# Accelerometer_3Axis-bak.net
KiCad netlist of a schematic drawn in Altium Designer
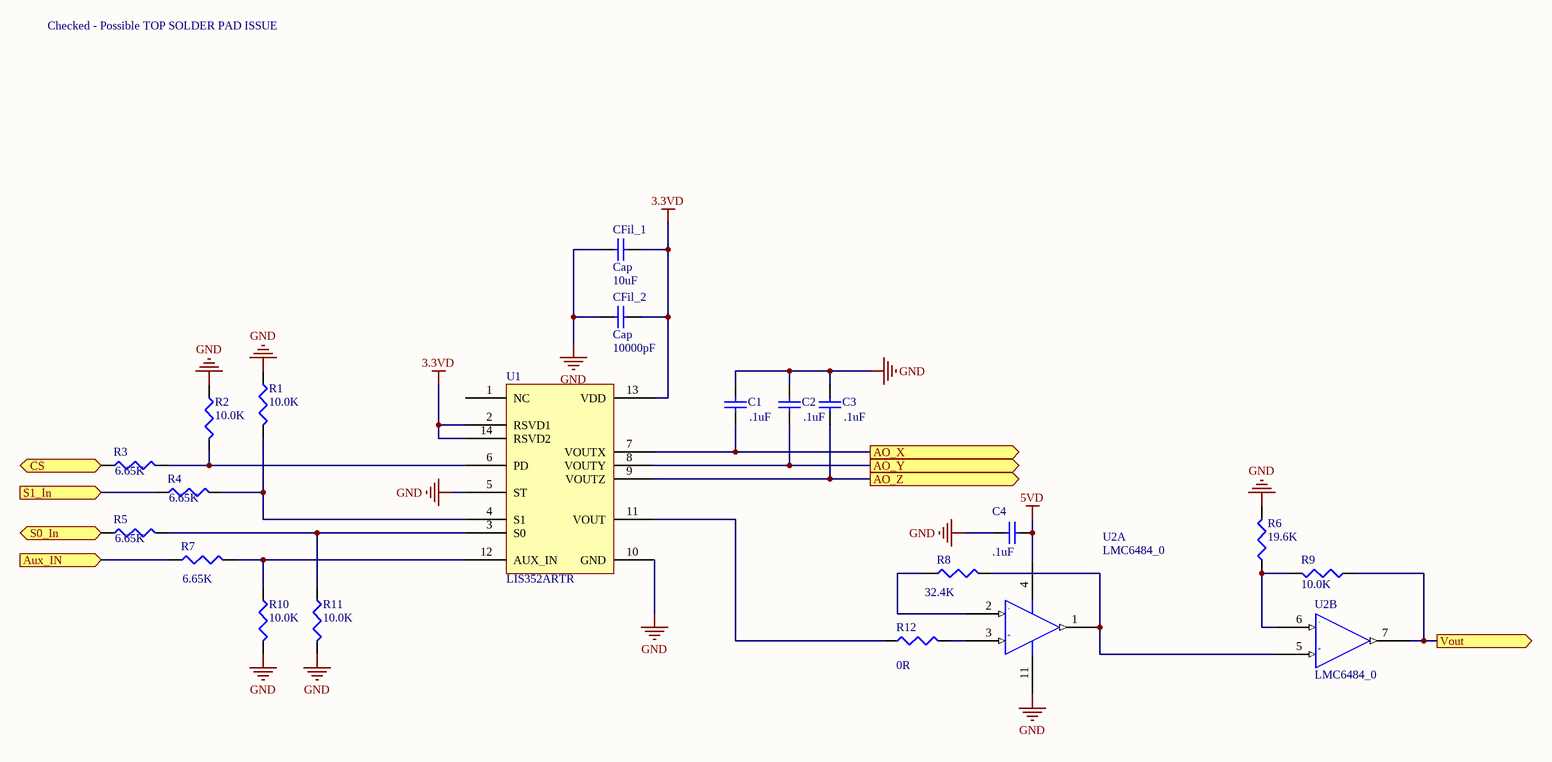
[diagram p0: Accelerometer_3Axis-bak.SchDoc]

(export (version "E")
  (design (tool "Eeschema 10.0.6"))
  (components
    (comp (ref "C1")
      (value ".1uF")
      (footprint "CAPC2012X09M")
      (description "CAP CER .1uF 50v Y5V 0805")
      (fields (field (name "TOLERANCE") "+80%/-20%") (field (name "MPN") "C0805C104Z5VACTU"))
      (libsource (lib "esd_library") (part "CAP-Y5V-.1uF-50V-+80%/-20%"))
    )
    (comp (ref "C2")
      (value ".1uF")
      (footprint "CAPC2012X09M")
      (description "CAP CER .1uF 50v Y5V 0805")
      (fields (field (name "TOLERANCE") "+80%/-20%") (field (name "MPN") "C0805C104Z5VACTU"))
      (libsource (lib "esd_library") (part "CAP-Y5V-.1uF-50V-+80%/-20%"))
    )
    (comp (ref "C3")
      (value ".1uF")
      (footprint "CAPC2012X09M")
      (description "CAP CER .1uF 50v Y5V 0805")
      (fields (field (name "TOLERANCE") "+80%/-20%") (field (name "MPN") "C0805C104Z5VACTU"))
      (libsource (lib "esd_library") (part "CAP-Y5V-.1uF-50V-+80%/-20%"))
    )
    (comp (ref "C4")
      (value ".1uF")
      (footprint "CAPC2012X09M")
      (description "CAP CER .1uF 50v X7R 0805")
      (fields (field (name "MPN") "C0805C104M5RACTU") (field (name "Comment") "Cap"))
      (libsource (lib "esd_library") (part "CAP-X7R-.1uF-50V-±20%"))
    )
    (comp (ref "CFil_1")
      (value "Cap")
      (footprint "CAPC2012X09M")
      (description "CAP CER 10uF 6.3v X5R 0805")
      (fields (field (name "ALTIUM_VALUE") "10uF") (field (name "MPN") "C0805C106K9PACTU"))
      (libsource (lib "esd_library") (part "CAP-X5R-10uF-6.3V-±10%"))
    )
    (comp (ref "CFil_2")
      (value "Cap")
      (footprint "CAPC2012X09M")
      (description "CAP CER 10000pF 50v Z5U 0805")
      (fields (field (name "ALTIUM_VALUE") "10000pF") (field (name "MPN") "C0805C103M5UACTU"))
      (libsource (lib "esd_library") (part "CAP-Z5U-10000pF-50V-±20%"))
    )
    (comp (ref "R1")
      (value "10.0K")
      (footprint "RESC2112X05M")
      (description "RES SMD 10.0K OHM 1% 1/8W 0805")
      (fields (field (name "MPN") "CRCW080510K0FKEA") (field (name "Comment") "Res3"))
      (libsource (lib "esd_library") (part "Resistor_10.0K"))
    )
    (comp (ref "R2")
      (value "10.0K")
      (footprint "RESC2112X05M")
      (description "RES SMD 10.0K OHM 1% 1/8W 0805")
      (fields (field (name "MPN") "CRCW080510K0FKEA") (field (name "Comment") "Res3"))
      (libsource (lib "esd_library") (part "Resistor_10.0K"))
    )
    (comp (ref "R3")
      (value "6.65K")
      (footprint "RESC2112X05M")
      (description "RES SMD 6.65K OHM 1% 1/8W 0805")
      (fields (field (name "MPN") "CRCW08056K65FKEA") (field (name "Comment") "Res3"))
      (libsource (lib "esd_library") (part "Resistor_6.65K"))
    )
    (comp (ref "R4")
      (value "6.65K")
      (footprint "RESC2112X05M")
      (description "RES SMD 6.65K OHM 1% 1/8W 0805")
      (fields (field (name "MPN") "CRCW08056K65FKEA") (field (name "Comment") "Res3"))
      (libsource (lib "esd_library") (part "Resistor_6.65K"))
    )
    (comp (ref "R5")
      (value "6.65K")
      (footprint "RESC2112X05M")
      (description "RES SMD 6.65K OHM 1% 1/8W 0805")
      (fields (field (name "MPN") "CRCW08056K65FKEA") (field (name "Comment") "Res3"))
      (libsource (lib "esd_library") (part "Resistor_6.65K"))
    )
    (comp (ref "R6")
      (value "19.6K")
      (footprint "RESC2112X05M")
      (description "RES SMD 19.6K OHM 1% 1/8W 0805")
      (fields (field (name "MPN") "CRCW080519K6FKEA") (field (name "Comment") "Res3"))
      (libsource (lib "esd_library (1)") (part "Resistor_19.6K"))
    )
    (comp (ref "R7")
      (value "6.65K")
      (footprint "RESC2112X05M")
      (description "RES SMD 6.65K OHM 1% 1/8W 0805")
      (fields (field (name "MPN") "CRCW08056K65FKEA") (field (name "Comment") "Res3"))
      (libsource (lib "esd_library") (part "Resistor_6.65K"))
    )
    (comp (ref "R8")
      (value "32.4K")
      (footprint "RESC2112X05M")
      (description "RES SMD 32.4K OHM 1% 1/8W 0805")
      (fields (field (name "MPN") "CRCW080532K4FKEA") (field (name "Comment") "Res3"))
      (libsource (lib "esd_library") (part "Resistor_32.4K"))
    )
    (comp (ref "R9")
      (value "10.0K")
      (footprint "RESC2112X05M")
      (description "RES SMD 10.0K OHM 1% 1/8W 0805")
      (fields (field (name "MPN") "CRCW080510K0FKEA") (field (name "Comment") "Res3"))
      (libsource (lib "esd_library") (part "Resistor_10.0K"))
    )
    (comp (ref "R10")
      (value "10.0K")
      (footprint "RESC2112X05M")
      (description "RES SMD 10.0K OHM 1% 1/8W 0805")
      (fields (field (name "MPN") "CRCW080510K0FKEA") (field (name "Comment") "Res3"))
      (libsource (lib "esd_library") (part "Resistor_10.0K"))
    )
    (comp (ref "R11")
      (value "10.0K")
      (footprint "RESC2112X05M")
      (description "RES SMD 10.0K OHM 1% 1/8W 0805")
      (fields (field (name "MPN") "CRCW080510K0FKEA") (field (name "Comment") "Res3"))
      (libsource (lib "esd_library") (part "Resistor_10.0K"))
    )
    (comp (ref "R12")
      (value "0R")
      (footprint "RESC2112X05M")
      (description "RES SMD 0 OHM 5% 1/8W 0805")
      (fields (field (name "MPN") "CRCW08050000Z0EA") (field (name "Comment") "Res3"))
      (libsource (lib "esd_library") (part "Resistor_0R_Jumper"))
    )
    (comp (ref "U1")
      (value "LIS352ARTR")
      (footprint "LGA-14-3X5MM")
      (description "IC ACCELEROMETER 3AXIS LP 14LGA")
      (libsource (lib "esd_library") (part "LIS352AR"))
    )
    (comp (ref "U2")
      (value "LMC6484_0")
      (footprint "SOIC127P600X175-14M-NS")
      (description "IC OPAMP GP 1.5MHZ RRO 14SOIC")
      (fields (field (name "MPN") "LMC6484IMX/NOPB"))
      (libsource (lib "esd_library") (part "LMC6484_0"))
    )
  )
  (nets
    (net (code "1") (name "/AO_X") (class "Default")
      (node (ref "C1") (pin "1") (pinfunction "1_1") (pintype "passive"))
      (node (ref "U1") (pin "7") (pinfunction "VOUTX_7") (pintype "passive"))
    )
    (net (code "2") (name "/AO_Y") (class "Default")
      (node (ref "C2") (pin "1") (pinfunction "1_1") (pintype "passive"))
      (node (ref "U1") (pin "8") (pinfunction "VOUTY_8") (pintype "passive"))
    )
    (net (code "3") (name "/AO_Z") (class "Default")
      (node (ref "C3") (pin "1") (pinfunction "1_1") (pintype "passive"))
      (node (ref "U1") (pin "9") (pinfunction "VOUTZ_9") (pintype "passive"))
    )
    (net (code "4") (name "/Aux_IN") (class "Default")
      (node (ref "R7") (pin "1") (pinfunction "1_1") (pintype "passive"))
    )
    (net (code "5") (name "/CS") (class "Default")
      (node (ref "R3") (pin "1") (pinfunction "1_1") (pintype "passive"))
    )
    (net (code "6") (name "/S0_In") (class "Default")
      (node (ref "R5") (pin "1") (pinfunction "1_1") (pintype "passive"))
    )
    (net (code "7") (name "/S1_In") (class "Default")
      (node (ref "R4") (pin "1") (pinfunction "1_1") (pintype "passive"))
    )
    (net (code "8") (name "/Vout") (class "Default")
      (node (ref "R9") (pin "1") (pinfunction "1_1") (pintype "passive"))
      (node (ref "U2") (pin "7") (pinfunction "OUT2_7") (pintype "output"))
    )
    (net (code "9") (name "3.3VD") (class "Default")
      (node (ref "CFil_1") (pin "1") (pinfunction "1_1") (pintype "passive"))
      (node (ref "CFil_2") (pin "1") (pinfunction "1_1") (pintype "passive"))
      (node (ref "U1") (pin "13") (pinfunction "VDD_13") (pintype "passive"))
      (node (ref "U1") (pin "14") (pinfunction "RSVD2_14") (pintype "passive"))
      (node (ref "U1") (pin "2") (pinfunction "RSVD1_2") (pintype "passive"))
    )
    (net (code "10") (name "5VD") (class "Default")
      (node (ref "C4") (pin "2") (pinfunction "2_2") (pintype "passive"))
      (node (ref "U2") (pin "4") (pinfunction "VCC_4") (pintype "power_in"))
    )
    (net (code "11") (name "GND") (class "Default")
      (node (ref "C1") (pin "2") (pinfunction "2_2") (pintype "passive"))
      (node (ref "C2") (pin "2") (pinfunction "2_2") (pintype "passive"))
      (node (ref "C3") (pin "2") (pinfunction "2_2") (pintype "passive"))
      (node (ref "C4") (pin "1") (pinfunction "1_1") (pintype "passive"))
      (node (ref "CFil_1") (pin "2") (pinfunction "2_2") (pintype "passive"))
      (node (ref "CFil_2") (pin "2") (pinfunction "2_2") (pintype "passive"))
      (node (ref "R1") (pin "1") (pinfunction "1_1") (pintype "passive"))
      (node (ref "R10") (pin "2") (pinfunction "2_2") (pintype "passive"))
      (node (ref "R11") (pin "2") (pinfunction "2_2") (pintype "passive"))
      (node (ref "R2") (pin "1") (pinfunction "1_1") (pintype "passive"))
      (node (ref "R6") (pin "2") (pinfunction "2_2") (pintype "passive"))
      (node (ref "U1") (pin "10") (pinfunction "GND_10") (pintype "passive"))
      (node (ref "U1") (pin "5") (pinfunction "ST_5") (pintype "passive"))
      (node (ref "U2") (pin "11") (pinfunction "-VCC_11") (pintype "power_in"))
    )
    (net (code "12") (name "Net-(U1-AUX_IN)") (class "Default")
      (node (ref "R10") (pin "1") (pinfunction "1_1") (pintype "passive"))
      (node (ref "R7") (pin "2") (pinfunction "2_2") (pintype "passive"))
      (node (ref "U1") (pin "12") (pinfunction "AUX_IN_12") (pintype "passive"))
    )
    (net (code "13") (name "Net-(U1-PD)") (class "Default")
      (node (ref "R2") (pin "2") (pinfunction "2_2") (pintype "passive"))
      (node (ref "R3") (pin "2") (pinfunction "2_2") (pintype "passive"))
      (node (ref "U1") (pin "6") (pinfunction "PD_6") (pintype "passive"))
    )
    (net (code "14") (name "Net-(U1-S0)") (class "Default")
      (node (ref "R11") (pin "1") (pinfunction "1_1") (pintype "passive"))
      (node (ref "R5") (pin "2") (pinfunction "2_2") (pintype "passive"))
      (node (ref "U1") (pin "3") (pinfunction "S0_3") (pintype "passive"))
    )
    (net (code "15") (name "Net-(U1-S1)") (class "Default")
      (node (ref "R1") (pin "2") (pinfunction "2_2") (pintype "passive"))
      (node (ref "R4") (pin "2") (pinfunction "2_2") (pintype "passive"))
      (node (ref "U1") (pin "4") (pinfunction "S1_4") (pintype "passive"))
    )
    (net (code "16") (name "Net-(U1-VOUT)") (class "Default")
      (node (ref "R12") (pin "1") (pinfunction "1_1") (pintype "passive"))
      (node (ref "U1") (pin "11") (pinfunction "VOUT_11") (pintype "passive"))
    )
    (net (code "17") (name "Net-(U2A-INVIN_1)") (class "Default")
      (node (ref "R8") (pin "1") (pinfunction "1_1") (pintype "passive"))
      (node (ref "U2") (pin "2") (pinfunction "INVIN_1_2") (pintype "input"))
    )
    (net (code "18") (name "Net-(U2A-NINVIN_1)") (class "Default")
      (node (ref "R12") (pin "2") (pinfunction "2_2") (pintype "passive"))
      (node (ref "U2") (pin "3") (pinfunction "NINVIN_1_3") (pintype "input"))
    )
    (net (code "19") (name "Net-(U2A-OUT1)") (class "Default")
      (node (ref "R8") (pin "2") (pinfunction "2_2") (pintype "passive"))
      (node (ref "U2") (pin "1") (pinfunction "OUT1_1") (pintype "output"))
      (node (ref "U2") (pin "5") (pinfunction "NINVIN2_5") (pintype "input"))
    )
    (net (code "20") (name "Net-(U2B-INVIN2)") (class "Default")
      (node (ref "R6") (pin "1") (pinfunction "1_1") (pintype "passive"))
      (node (ref "R9") (pin "2") (pinfunction "2_2") (pintype "passive"))
      (node (ref "U2") (pin "6") (pinfunction "INVIN2_6") (pintype "input"))
    )
    (net (code "21") (name "unconnected-(U1-NC-Pad1)") (class "Default")
      (node (ref "U1") (pin "1") (pinfunction "NC_1") (pintype "passive"))
    )
  )
)
